# DIOT-mini-backplane.net
KiCad netlist of a schematic drawn in Altium Designer
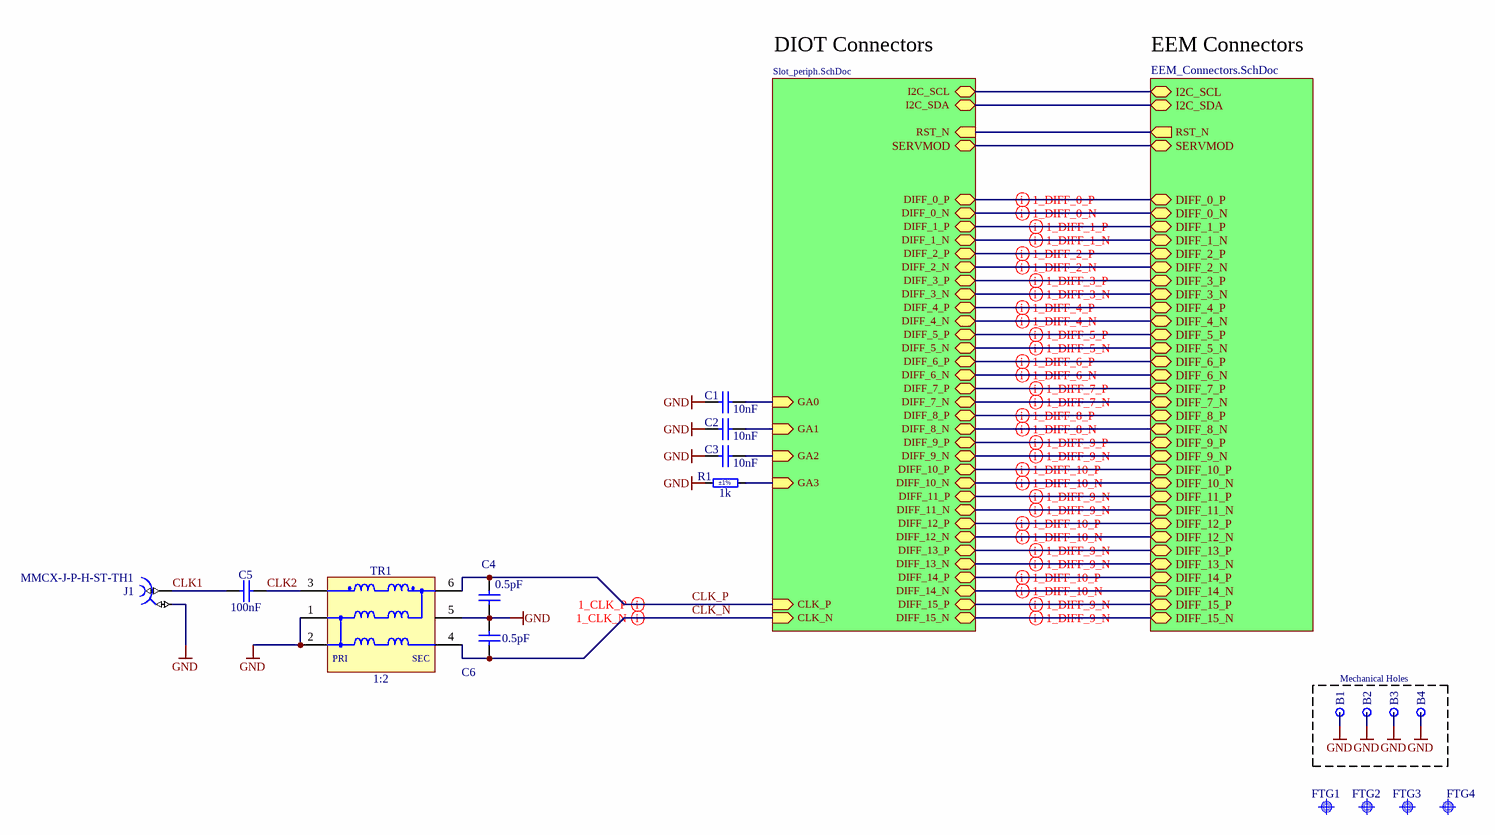
[diagram p0: DIOT-mini-backplane.SchDoc]

(export (version "E")
  (design (tool "Eeschema 10.0.6"))
  (components
    (comp (ref "B1")
      (value "Non Plated Hole")
      (footprint "MTG270_500_NPTH_8FCVIAS_BOTSM")
      (description "Single Terminal Socket")
      (fields
        (field (name "PART NUMBER") "NON-PLATED_HOLE2.7_PAD5.0_8FCVIAS_BOTSM")
        (field (name "AUTHOR") "CERN DEM WB")
      )
      (libsource (lib "Eletro-mechanical") (part "Single Terminal Socket"))
    )
    (comp (ref "B2")
      (value "Non Plated Hole")
      (footprint "MTG270_500_NPTH_8FCVIAS_BOTSM")
      (description "Single Terminal Socket")
      (fields
        (field (name "PART NUMBER") "NON-PLATED_HOLE2.7_PAD5.0_8FCVIAS_BOTSM")
        (field (name "AUTHOR") "CERN DEM WB")
      )
      (libsource (lib "Eletro-mechanical") (part "Single Terminal Socket"))
    )
    (comp (ref "B3")
      (value "Non Plated Hole")
      (footprint "MTG270_500_NPTH_8FCVIAS_BOTSM")
      (description "Single Terminal Socket")
      (fields
        (field (name "PART NUMBER") "NON-PLATED_HOLE2.7_PAD5.0_8FCVIAS_BOTSM")
        (field (name "AUTHOR") "CERN DEM WB")
      )
      (libsource (lib "Eletro-mechanical") (part "Single Terminal Socket"))
    )
    (comp (ref "B4")
      (value "Non Plated Hole")
      (footprint "MTG270_500_NPTH_8FCVIAS_BOTSM")
      (description "Single Terminal Socket")
      (fields
        (field (name "PART NUMBER") "NON-PLATED_HOLE2.7_PAD5.0_8FCVIAS_BOTSM")
        (field (name "AUTHOR") "CERN DEM WB")
      )
      (libsource (lib "Eletro-mechanical") (part "Single Terminal Socket"))
    )
    (comp (ref "C1")
      (value "10nF")
      (footprint "CAPC1005X55N")
      (description "Non-polarised capacitor")
      (fields
        (field (name "PART NUMBER") "CC0402_10NF_16V_10%_X7R")
        (field (name "VOLTAGE") "16V")
        (field (name "AUTHOR") "CERN DEM JLC")
      )
      (libsource (lib "Capacitors") (part "Capacitor - non polarized"))
    )
    (comp (ref "C2")
      (value "10nF")
      (footprint "CAPC1005X55N")
      (description "Non-polarised capacitor")
      (fields
        (field (name "PART NUMBER") "CC0402_10NF_16V_10%_X7R")
        (field (name "VOLTAGE") "16V")
        (field (name "AUTHOR") "CERN DEM JLC")
      )
      (libsource (lib "Capacitors") (part "Capacitor - non polarized"))
    )
    (comp (ref "C3")
      (value "10nF")
      (footprint "CAPC1005X55N")
      (description "Non-polarised capacitor")
      (fields
        (field (name "PART NUMBER") "CC0402_10NF_16V_10%_X7R")
        (field (name "VOLTAGE") "16V")
        (field (name "AUTHOR") "CERN DEM JLC")
      )
      (libsource (lib "Capacitors") (part "Capacitor - non polarized"))
    )
    (comp (ref "C4")
      (value "0.5pF")
      (footprint "CAPC1005X50N")
      (description "Non-polarised capacitor")
      (fields
        (field (name "PART NUMBER") "CC0402_0.5PF_25V_0.05PF_AVX_04023J0R5ABSTR")
        (field (name "VOLTAGE") "25V")
        (field (name "AUTHOR") "CERN DEM JLC")
      )
      (libsource (lib "Capacitors") (part "Capacitor - non polarized"))
    )
    (comp (ref "C5")
      (value "100nF")
      (footprint "CAPC1005X55N")
      (description "Non-polarised capacitor")
      (fields
        (field (name "PART NUMBER") "CC0402_100NF_16V_10%_X7R")
        (field (name "VOLTAGE") "16V")
        (field (name "AUTHOR") "CERN DEM JLC")
      )
      (libsource (lib "Capacitors") (part "Capacitor - non polarized"))
    )
    (comp (ref "C6")
      (value "0.5pF")
      (footprint "CAPC1005X50N")
      (description "Non-polarised capacitor")
      (fields
        (field (name "PART NUMBER") "CC0402_0.5PF_25V_0.05PF_AVX_04023J0R5ABSTR")
        (field (name "VOLTAGE") "25V")
        (field (name "AUTHOR") "CERN DEM JLC")
      )
      (libsource (lib "Capacitors") (part "Capacitor - non polarized"))
    )
    (comp (ref "FTG1")
      (value "Use only in PCB")
      (footprint "FIDUCIAL_TOP_C100-200")
      (description "Fiducial Target")
      (fields (field (name "PART NUMBER") "FIDUCIAL_TARGET_C100-200") (field (name "AUTHOR") "CERN DEM JLC"))
      (libsource (lib "Eletro-mechanical") (part "Fiducial Target"))
    )
    (comp (ref "FTG2")
      (value "Use only in PCB")
      (footprint "FIDUCIAL_TOP_C100-200")
      (description "Fiducial Target")
      (fields (field (name "PART NUMBER") "FIDUCIAL_TARGET_C100-200") (field (name "AUTHOR") "CERN DEM JLC"))
      (libsource (lib "Eletro-mechanical") (part "Fiducial Target"))
    )
    (comp (ref "FTG3")
      (value "Use only in PCB")
      (footprint "FIDUCIAL_TOP_C100-200")
      (description "Fiducial Target")
      (fields (field (name "PART NUMBER") "FIDUCIAL_TARGET_C100-200") (field (name "AUTHOR") "CERN DEM JLC"))
      (libsource (lib "Eletro-mechanical") (part "Fiducial Target"))
    )
    (comp (ref "FTG4")
      (value "Use only in PCB")
      (footprint "FIDUCIAL_TOP_C100-200")
      (description "Fiducial Target")
      (fields (field (name "PART NUMBER") "FIDUCIAL_TARGET_C100-200") (field (name "AUTHOR") "CERN DEM JLC"))
      (libsource (lib "Eletro-mechanical") (part "Fiducial Target"))
    )
    (comp (ref "J1")
      (value "MMCX-J-P-H-ST-TH1")
      (footprint "SAMTEC_MMCX-J-P-H-ST-TH1")
      (fields
        (field (name "PART NUMBER") "SAMTEC_MMCX-J-P-H-ST-TH1")
        (field (name "MANUFACTURER") "SAMTEC")
        (field (name "AUTHOR") "CERN DEM JLC")
      )
      (libsource (lib "Connectors") (part "Coax_1Female_1Shield"))
    )
    (comp (ref "R1")
      (value "1k")
      (footprint "RESC1005X40N")
      (description "Resistor - 1%")
      (fields
        (field (name "TOLERANCE") "±1%")
        (field (name "PART NUMBER") "R0402_1K_1%_0.0625W_100PPM")
        (field (name "POWER") "0.0625W")
        (field (name "AUTHOR") "CERN DEM JLC")
      )
      (libsource (lib "Resistors") (part "Resistor - 1%"))
    )
    (comp (ref "TR1")
      (value "1:2")
      (footprint "XFMR_MINI-CIRCUITS_DB1627")
      (description "50 OHMS 10 to 4000 MHz RF Transformer")
      (fields
        (field (name "PART NUMBER") "XFMR_MINI-CIRCUITS_TCM2-43X+")
        (field (name "POWER") "0.4W")
        (field (name "AUTHOR") "CERN DEM BC")
      )
      (libsource (lib "Inductors & Transformers") (part "XFMR_MINI-CIRCUITS_TCM2-43X"))
    )
  )
  (nets
    (net (code "1") (name "/CLK1") (class "Default")
      (node (ref "C5") (pin "1") (pinfunction "1_1") (pintype "passive"))
      (node (ref "J1") (pin "1") (pinfunction "1_1") (pintype "bidirectional"))
    )
    (net (code "2") (name "/CLK2") (class "Default")
      (node (ref "C5") (pin "2") (pinfunction "2_2") (pintype "passive"))
      (node (ref "TR1") (pin "3") (pinfunction "P1_3") (pintype "passive"))
    )
    (net (code "3") (name "/CLK_N") (class "Default")
      (node (ref "C6") (pin "1") (pinfunction "1_1") (pintype "passive"))
      (node (ref "TR1") (pin "4") (pinfunction "S1_4") (pintype "passive"))
    )
    (net (code "4") (name "/CLK_P") (class "Default")
      (node (ref "C4") (pin "2") (pinfunction "2_2") (pintype "passive"))
      (node (ref "TR1") (pin "6") (pinfunction "S1_6") (pintype "passive"))
    )
    (net (code "37") (name "/GA0") (class "Default")
      (node (ref "C1") (pin "2") (pinfunction "2_2") (pintype "passive"))
    )
    (net (code "38") (name "/GA1") (class "Default")
      (node (ref "C2") (pin "2") (pinfunction "2_2") (pintype "passive"))
    )
    (net (code "39") (name "/GA2") (class "Default")
      (node (ref "C3") (pin "2") (pinfunction "2_2") (pintype "passive"))
    )
    (net (code "40") (name "/GA3") (class "Default")
      (node (ref "R1") (pin "2") (pinfunction "2_2") (pintype "passive"))
    )
    (net (code "45") (name "GND") (class "Default")
      (node (ref "B1") (pin "1") (pinfunction "1_1") (pintype "bidirectional"))
      (node (ref "B2") (pin "1") (pinfunction "1_1") (pintype "bidirectional"))
      (node (ref "B3") (pin "1") (pinfunction "1_1") (pintype "bidirectional"))
      (node (ref "B4") (pin "1") (pinfunction "1_1") (pintype "bidirectional"))
      (node (ref "C1") (pin "1") (pinfunction "1_1") (pintype "passive"))
      (node (ref "C2") (pin "1") (pinfunction "1_1") (pintype "passive"))
      (node (ref "C3") (pin "1") (pinfunction "1_1") (pintype "passive"))
      (node (ref "C4") (pin "1") (pinfunction "1_1") (pintype "passive"))
      (node (ref "C6") (pin "2") (pinfunction "2_2") (pintype "passive"))
      (node (ref "J1") (pin "2") (pinfunction "2_2") (pintype "bidirectional"))
      (node (ref "R1") (pin "1") (pinfunction "1_1") (pintype "passive"))
      (node (ref "TR1") (pin "1") (pinfunction "P1_1") (pintype "passive"))
      (node (ref "TR1") (pin "2") (pinfunction "P1_2") (pintype "passive"))
      (node (ref "TR1") (pin "5") (pinfunction "NC_5") (pintype "passive"))
    )
  )
)
